# FMC_Metlino_Fabric-Timing.net
KiCad netlist of a schematic drawn in Altium Designer
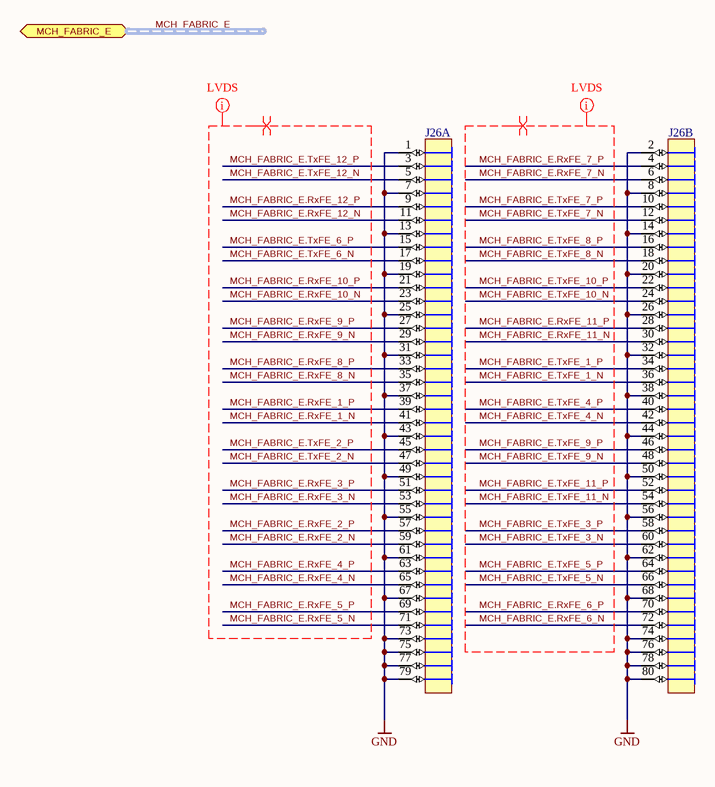
[diagram p0: FMC_Metlino_Fabric-Timing.SchDoc]

(export (version "E")
  (design (tool "Eeschema 10.0.6"))
  (components
    (comp (ref "J26")
      (value "~")
      (footprint "SAMTEC_FSI-140-XX-X-D-AD_bot")
      (fields
        (field (name "PART NUMBER") "SAMTEC_FSI-140-10-L-D-AD_bot")
        (field (name "AUTHOR") "CERN DEM BC")
      )
      (libsource (lib "Connectors") (part "SAMTEC_FSI-140-XX-X-D-AD_bot"))
    )
  )
  (nets
    (net (code "2") (name "/MCH_FABRIC_E.RxFE_1_N") (class "Default")
      (node (ref "J26") (pin "41") (pinfunction "41_41") (pintype "bidirectional"))
    )
    (net (code "3") (name "/MCH_FABRIC_E.RxFE_1_P") (class "Default")
      (node (ref "J26") (pin "39") (pinfunction "39_39") (pintype "bidirectional"))
    )
    (net (code "4") (name "/MCH_FABRIC_E.RxFE_2_N") (class "Default")
      (node (ref "J26") (pin "59") (pinfunction "59_59") (pintype "bidirectional"))
    )
    (net (code "5") (name "/MCH_FABRIC_E.RxFE_2_P") (class "Default")
      (node (ref "J26") (pin "57") (pinfunction "57_57") (pintype "bidirectional"))
    )
    (net (code "6") (name "/MCH_FABRIC_E.RxFE_3_N") (class "Default")
      (node (ref "J26") (pin "53") (pinfunction "53_53") (pintype "bidirectional"))
    )
    (net (code "7") (name "/MCH_FABRIC_E.RxFE_3_P") (class "Default")
      (node (ref "J26") (pin "51") (pinfunction "51_51") (pintype "bidirectional"))
    )
    (net (code "8") (name "/MCH_FABRIC_E.RxFE_4_N") (class "Default")
      (node (ref "J26") (pin "65") (pinfunction "65_65") (pintype "bidirectional"))
    )
    (net (code "9") (name "/MCH_FABRIC_E.RxFE_4_P") (class "Default")
      (node (ref "J26") (pin "63") (pinfunction "63_63") (pintype "bidirectional"))
    )
    (net (code "10") (name "/MCH_FABRIC_E.RxFE_5_N") (class "Default")
      (node (ref "J26") (pin "71") (pinfunction "71_71") (pintype "bidirectional"))
    )
    (net (code "11") (name "/MCH_FABRIC_E.RxFE_5_P") (class "Default")
      (node (ref "J26") (pin "69") (pinfunction "69_69") (pintype "bidirectional"))
    )
    (net (code "12") (name "/MCH_FABRIC_E.RxFE_6_N") (class "Default")
      (node (ref "J26") (pin "72") (pinfunction "72_72") (pintype "bidirectional"))
    )
    (net (code "13") (name "/MCH_FABRIC_E.RxFE_6_P") (class "Default")
      (node (ref "J26") (pin "70") (pinfunction "70_70") (pintype "bidirectional"))
    )
    (net (code "14") (name "/MCH_FABRIC_E.RxFE_7_N") (class "Default")
      (node (ref "J26") (pin "6") (pinfunction "6_6") (pintype "bidirectional"))
    )
    (net (code "15") (name "/MCH_FABRIC_E.RxFE_7_P") (class "Default")
      (node (ref "J26") (pin "4") (pinfunction "4_4") (pintype "bidirectional"))
    )
    (net (code "16") (name "/MCH_FABRIC_E.RxFE_8_N") (class "Default")
      (node (ref "J26") (pin "35") (pinfunction "35_35") (pintype "bidirectional"))
    )
    (net (code "17") (name "/MCH_FABRIC_E.RxFE_8_P") (class "Default")
      (node (ref "J26") (pin "33") (pinfunction "33_33") (pintype "bidirectional"))
    )
    (net (code "18") (name "/MCH_FABRIC_E.RxFE_9_N") (class "Default")
      (node (ref "J26") (pin "29") (pinfunction "29_29") (pintype "bidirectional"))
    )
    (net (code "19") (name "/MCH_FABRIC_E.RxFE_9_P") (class "Default")
      (node (ref "J26") (pin "27") (pinfunction "27_27") (pintype "bidirectional"))
    )
    (net (code "20") (name "/MCH_FABRIC_E.RxFE_10_N") (class "Default")
      (node (ref "J26") (pin "23") (pinfunction "23_23") (pintype "bidirectional"))
    )
    (net (code "21") (name "/MCH_FABRIC_E.RxFE_10_P") (class "Default")
      (node (ref "J26") (pin "21") (pinfunction "21_21") (pintype "bidirectional"))
    )
    (net (code "22") (name "/MCH_FABRIC_E.RxFE_11_N") (class "Default")
      (node (ref "J26") (pin "30") (pinfunction "30_30") (pintype "bidirectional"))
    )
    (net (code "23") (name "/MCH_FABRIC_E.RxFE_11_P") (class "Default")
      (node (ref "J26") (pin "28") (pinfunction "28_28") (pintype "bidirectional"))
    )
    (net (code "24") (name "/MCH_FABRIC_E.RxFE_12_N") (class "Default")
      (node (ref "J26") (pin "11") (pinfunction "11_11") (pintype "bidirectional"))
    )
    (net (code "25") (name "/MCH_FABRIC_E.RxFE_12_P") (class "Default")
      (node (ref "J26") (pin "9") (pinfunction "9_9") (pintype "bidirectional"))
    )
    (net (code "26") (name "/MCH_FABRIC_E.TxFE_1_N") (class "Default")
      (node (ref "J26") (pin "36") (pinfunction "36_36") (pintype "bidirectional"))
    )
    (net (code "27") (name "/MCH_FABRIC_E.TxFE_1_P") (class "Default")
      (node (ref "J26") (pin "34") (pinfunction "34_34") (pintype "bidirectional"))
    )
    (net (code "28") (name "/MCH_FABRIC_E.TxFE_2_N") (class "Default")
      (node (ref "J26") (pin "47") (pinfunction "47_47") (pintype "bidirectional"))
    )
    (net (code "29") (name "/MCH_FABRIC_E.TxFE_2_P") (class "Default")
      (node (ref "J26") (pin "45") (pinfunction "45_45") (pintype "bidirectional"))
    )
    (net (code "30") (name "/MCH_FABRIC_E.TxFE_3_N") (class "Default")
      (node (ref "J26") (pin "60") (pinfunction "60_60") (pintype "bidirectional"))
    )
    (net (code "31") (name "/MCH_FABRIC_E.TxFE_3_P") (class "Default")
      (node (ref "J26") (pin "58") (pinfunction "58_58") (pintype "bidirectional"))
    )
    (net (code "32") (name "/MCH_FABRIC_E.TxFE_4_N") (class "Default")
      (node (ref "J26") (pin "42") (pinfunction "42_42") (pintype "bidirectional"))
    )
    (net (code "33") (name "/MCH_FABRIC_E.TxFE_4_P") (class "Default")
      (node (ref "J26") (pin "40") (pinfunction "40_40") (pintype "bidirectional"))
    )
    (net (code "34") (name "/MCH_FABRIC_E.TxFE_5_N") (class "Default")
      (node (ref "J26") (pin "66") (pinfunction "66_66") (pintype "bidirectional"))
    )
    (net (code "35") (name "/MCH_FABRIC_E.TxFE_5_P") (class "Default")
      (node (ref "J26") (pin "64") (pinfunction "64_64") (pintype "bidirectional"))
    )
    (net (code "36") (name "/MCH_FABRIC_E.TxFE_6_N") (class "Default")
      (node (ref "J26") (pin "17") (pinfunction "17_17") (pintype "bidirectional"))
    )
    (net (code "37") (name "/MCH_FABRIC_E.TxFE_6_P") (class "Default")
      (node (ref "J26") (pin "15") (pinfunction "15_15") (pintype "bidirectional"))
    )
    (net (code "38") (name "/MCH_FABRIC_E.TxFE_7_N") (class "Default")
      (node (ref "J26") (pin "12") (pinfunction "12_12") (pintype "bidirectional"))
    )
    (net (code "39") (name "/MCH_FABRIC_E.TxFE_7_P") (class "Default")
      (node (ref "J26") (pin "10") (pinfunction "10_10") (pintype "bidirectional"))
    )
    (net (code "40") (name "/MCH_FABRIC_E.TxFE_8_N") (class "Default")
      (node (ref "J26") (pin "18") (pinfunction "18_18") (pintype "bidirectional"))
    )
    (net (code "41") (name "/MCH_FABRIC_E.TxFE_8_P") (class "Default")
      (node (ref "J26") (pin "16") (pinfunction "16_16") (pintype "bidirectional"))
    )
    (net (code "42") (name "/MCH_FABRIC_E.TxFE_9_N") (class "Default")
      (node (ref "J26") (pin "48") (pinfunction "48_48") (pintype "bidirectional"))
    )
    (net (code "43") (name "/MCH_FABRIC_E.TxFE_9_P") (class "Default")
      (node (ref "J26") (pin "46") (pinfunction "46_46") (pintype "bidirectional"))
    )
    (net (code "44") (name "/MCH_FABRIC_E.TxFE_10_N") (class "Default")
      (node (ref "J26") (pin "24") (pinfunction "24_24") (pintype "bidirectional"))
    )
    (net (code "45") (name "/MCH_FABRIC_E.TxFE_10_P") (class "Default")
      (node (ref "J26") (pin "22") (pinfunction "22_22") (pintype "bidirectional"))
    )
    (net (code "46") (name "/MCH_FABRIC_E.TxFE_11_N") (class "Default")
      (node (ref "J26") (pin "54") (pinfunction "54_54") (pintype "bidirectional"))
    )
    (net (code "47") (name "/MCH_FABRIC_E.TxFE_11_P") (class "Default")
      (node (ref "J26") (pin "52") (pinfunction "52_52") (pintype "bidirectional"))
    )
    (net (code "48") (name "/MCH_FABRIC_E.TxFE_12_N") (class "Default")
      (node (ref "J26") (pin "5") (pinfunction "5_5") (pintype "bidirectional"))
    )
    (net (code "49") (name "/MCH_FABRIC_E.TxFE_12_P") (class "Default")
      (node (ref "J26") (pin "3") (pinfunction "3_3") (pintype "bidirectional"))
    )
    (net (code "51") (name "GND") (class "Default")
      (node (ref "J26") (pin "1") (pinfunction "1_1") (pintype "bidirectional"))
      (node (ref "J26") (pin "13") (pinfunction "13_13") (pintype "bidirectional"))
      (node (ref "J26") (pin "14") (pinfunction "14_14") (pintype "bidirectional"))
      (node (ref "J26") (pin "19") (pinfunction "19_19") (pintype "bidirectional"))
      (node (ref "J26") (pin "2") (pinfunction "2_2") (pintype "bidirectional"))
      (node (ref "J26") (pin "20") (pinfunction "20_20") (pintype "bidirectional"))
      (node (ref "J26") (pin "25") (pinfunction "25_25") (pintype "bidirectional"))
      (node (ref "J26") (pin "26") (pinfunction "26_26") (pintype "bidirectional"))
      (node (ref "J26") (pin "31") (pinfunction "31_31") (pintype "bidirectional"))
      (node (ref "J26") (pin "32") (pinfunction "32_32") (pintype "bidirectional"))
      (node (ref "J26") (pin "37") (pinfunction "37_37") (pintype "bidirectional"))
      (node (ref "J26") (pin "38") (pinfunction "38_38") (pintype "bidirectional"))
      (node (ref "J26") (pin "43") (pinfunction "43_43") (pintype "bidirectional"))
      (node (ref "J26") (pin "44") (pinfunction "44_44") (pintype "bidirectional"))
      (node (ref "J26") (pin "49") (pinfunction "49_49") (pintype "bidirectional"))
      (node (ref "J26") (pin "50") (pinfunction "50_50") (pintype "bidirectional"))
      (node (ref "J26") (pin "55") (pinfunction "55_55") (pintype "bidirectional"))
      (node (ref "J26") (pin "56") (pinfunction "56_56") (pintype "bidirectional"))
      (node (ref "J26") (pin "61") (pinfunction "61_61") (pintype "bidirectional"))
      (node (ref "J26") (pin "62") (pinfunction "62_62") (pintype "bidirectional"))
      (node (ref "J26") (pin "67") (pinfunction "67_67") (pintype "bidirectional"))
      (node (ref "J26") (pin "68") (pinfunction "68_68") (pintype "bidirectional"))
      (node (ref "J26") (pin "7") (pinfunction "7_7") (pintype "bidirectional"))
      (node (ref "J26") (pin "73") (pinfunction "73_73") (pintype "bidirectional"))
      (node (ref "J26") (pin "74") (pinfunction "74_74") (pintype "bidirectional"))
      (node (ref "J26") (pin "75") (pinfunction "75_75") (pintype "bidirectional"))
      (node (ref "J26") (pin "76") (pinfunction "76_76") (pintype "bidirectional"))
      (node (ref "J26") (pin "77") (pinfunction "77_77") (pintype "bidirectional"))
      (node (ref "J26") (pin "78") (pinfunction "78_78") (pintype "bidirectional"))
      (node (ref "J26") (pin "79") (pinfunction "79_79") (pintype "bidirectional"))
      (node (ref "J26") (pin "8") (pinfunction "8_8") (pintype "bidirectional"))
      (node (ref "J26") (pin "80") (pinfunction "80_80") (pintype "bidirectional"))
    )
  )
)
